# cm_filter_ch1_b.net
KiCad netlist of a schematic drawn in Altium Designer
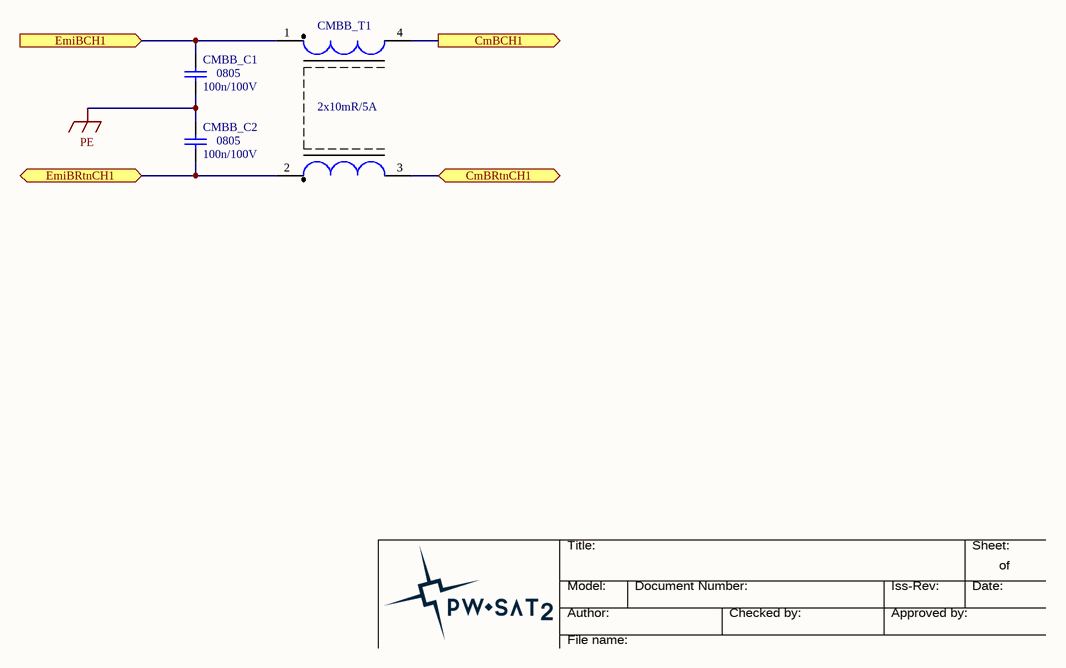
[diagram p0: cm_filter_ch1_b.SchDoc]

(export (version "E")
  (design (tool "Eeschema 10.0.6"))
  (components
    (comp (ref "CMBB_C1")
      (value "100n/100V")
      (footprint "SMD_Capacitor_0805")
      (description "Ceramic Cap Kemet COTS 100n/100V X7R 0805")
      (fields
        (field (name "MANUFACTURERPARTNUMBER") "C0805T104K1RCLTU")
        (field (name "MANUFACTURER") "Kemet")
        (field (name "PACKAGE") "0805")
      )
      (libsource (lib "capacitors") (part "Cer_C0805T104K1RCLTU"))
    )
    (comp (ref "CMBB_C2")
      (value "100n/100V")
      (footprint "SMD_Capacitor_0805")
      (description "Ceramic Cap Kemet COTS 100n/100V X7R 0805")
      (fields
        (field (name "MANUFACTURERPARTNUMBER") "C0805T104K1RCLTU")
        (field (name "MANUFACTURER") "Kemet")
        (field (name "PACKAGE") "0805")
      )
      (libsource (lib "capacitors") (part "Cer_C0805T104K1RCLTU"))
    )
    (comp (ref "CMBB_T1")
      (value "2x10mR/5A")
      (footprint "TDK_ACM7060")
      (description "TDK ACM7060-301 Common Mode Choke")
      (fields
        (field (name "MANUFACTURER") "TDK")
        (field (name "MANUFACTURERPARTNUMBER") "ACM7060-301-2PL-TL01")
      )
      (libsource (lib "inductors_cores") (part "ACM7060-301-2PL-TL01"))
    )
  )
  (nets
    (net (code "1") (name "/CmBCH1") (class "Default")
      (node (ref "CMBB_T1") (pin "4") (pinfunction "4_4") (pintype "passive"))
    )
    (net (code "2") (name "/CmBRtnCH1") (class "Default")
      (node (ref "CMBB_T1") (pin "3") (pinfunction "3_3") (pintype "passive"))
    )
    (net (code "3") (name "/EmiBCH1") (class "Default")
      (node (ref "CMBB_C1") (pin "1") (pinfunction "1_1") (pintype "passive"))
      (node (ref "CMBB_T1") (pin "1") (pinfunction "1_1") (pintype "passive"))
    )
    (net (code "4") (name "/EmiBRtnCH1") (class "Default")
      (node (ref "CMBB_C2") (pin "2") (pinfunction "2_2") (pintype "passive"))
      (node (ref "CMBB_T1") (pin "2") (pinfunction "2_2") (pintype "passive"))
    )
    (net (code "5") (name "PE") (class "Default")
      (node (ref "CMBB_C1") (pin "2") (pinfunction "2_2") (pintype "passive"))
      (node (ref "CMBB_C2") (pin "1") (pinfunction "1_1") (pintype "passive"))
    )
  )
)
